# lightmeter_2.net
KiCad netlist of a schematic drawn in EAGLE
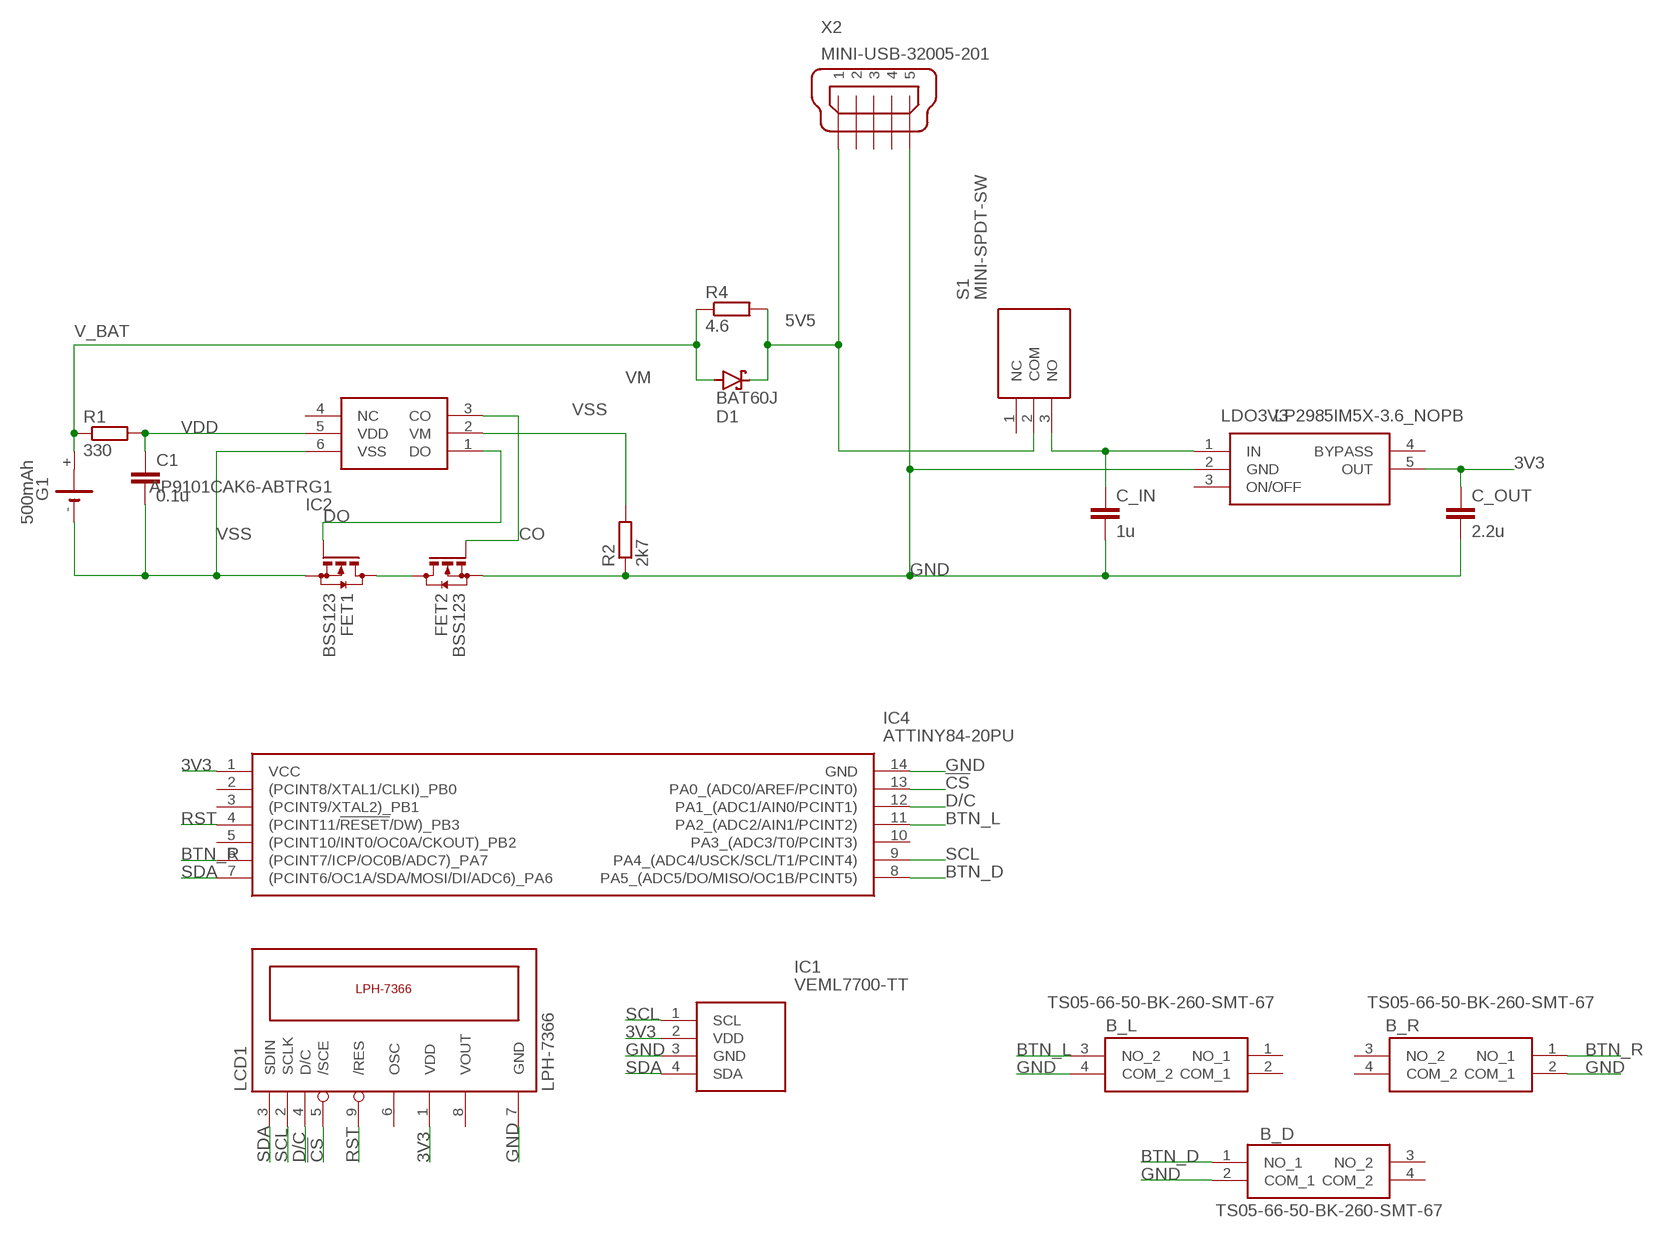
[diagram p0: schematic, sheet 1]

(export (version "E")
  (design (tool "Eeschema 10.0.6"))
  (components
    (comp (ref "B_D")
      (value "TS05-66-50-BK-260-SMT-67")
      (footprint "eagle-import:TS056650BK260SMT67")
      (fields (field (name "MOUSER_PART_NUMBER") "179-TS056650260SMT67"))
      (libsource (lib "eagle-import") (part "TS05-66-50-BK-260-SMT-67"))
    )
    (comp (ref "B_L")
      (value "TS05-66-50-BK-260-SMT-67")
      (footprint "eagle-import:TS056650BK260SMT67")
      (fields (field (name "MOUSER_PART_NUMBER") "179-TS056650260SMT67"))
      (libsource (lib "eagle-import") (part "TS05-66-50-BK-260-SMT-67"))
    )
    (comp (ref "B_R")
      (value "TS05-66-50-BK-260-SMT-67")
      (footprint "eagle-import:TS056650BK260SMT67")
      (fields (field (name "MOUSER_PART_NUMBER") "179-TS056650260SMT67"))
      (libsource (lib "eagle-import") (part "TS05-66-50-BK-260-SMT-67"))
    )
    (comp (ref "C1")
      (value "0.1u")
      (footprint "eagle-import:C3216")
      (libsource (lib "eagle-import") (part "C-EUC3216"))
    )
    (comp (ref "C_IN")
      (value "1u")
      (footprint "eagle-import:C3216")
      (libsource (lib "eagle-import") (part "C-EUC3216"))
    )
    (comp (ref "C_OUT")
      (value "2.2u")
      (footprint "eagle-import:C3216")
      (libsource (lib "eagle-import") (part "C-EUC3216"))
    )
    (comp (ref "D1")
      (value "BAT60J")
      (footprint "eagle-import:SOD323_ST")
      (libsource (lib "eagle-import") (part "BAT60J"))
    )
    (comp (ref "FET1")
      (value "BSS123")
      (footprint "eagle-import:SOT23")
      (libsource (lib "eagle-import") (part "BSS123"))
    )
    (comp (ref "FET2")
      (value "BSS123")
      (footprint "eagle-import:SOT23")
      (libsource (lib "eagle-import") (part "BSS123"))
    )
    (comp (ref "G1")
      (value "500mAh")
      (footprint "eagle-import:CR1_2")
      (libsource (lib "eagle-import") (part "CR1/2"))
    )
    (comp (ref "IC1")
      (value "VEML7700-TT")
      (footprint "eagle-import:VEML7700")
      (fields (field (name "MOUSER_PART_NUMBER") "78-VEML7700-TT"))
      (libsource (lib "eagle-import") (part "VEML7700-TT"))
    )
    (comp (ref "IC2")
      (value "AP9101CAK6-ABTRG1")
      (footprint "eagle-import:SOT95P285X140-6N")
      (fields (field (name "MOUSER_PART_NUMBER") "621-AP9101CAK6ABTRG1"))
      (libsource (lib "eagle-import") (part "AP9101CAK6-ABTRG1"))
    )
    (comp (ref "IC4")
      (value "ATTINY84-20PU")
      (footprint "eagle-import:DIP794W56P254L1918H533Q14N")
      (fields (field (name "MOUSER_PART_NUMBER") "556-ATTINY84-20PU"))
      (libsource (lib "eagle-import") (part "ATTINY84-20PU"))
    )
    (comp (ref "LCD1")
      (value "LPH-7366")
      (footprint "eagle-import:LPH-7366")
      (libsource (lib "eagle-import") (part "LPH-7366"))
    )
    (comp (ref "LDO3V3")
      (value "LP2985IM5X-3.6_NOPB")
      (footprint "eagle-import:SOT95P280X145-5N")
      (fields
        (field (name "MANUFACTURER_PART_NUMBER") "LP2985IM5X-3.6/NOPB")
        (field (name "MOUSER_PART_NUMBER") "926-LP2985IM5X36NOPB")
      )
      (libsource (lib "eagle-import") (part "LP2985IM5X-3.6_NOPB"))
    )
    (comp (ref "R1")
      (value "330")
      (footprint "eagle-import:R3216W")
      (libsource (lib "eagle-import") (part "R-EU_R3216W"))
    )
    (comp (ref "R2")
      (value "2k7")
      (footprint "eagle-import:R3216W")
      (libsource (lib "eagle-import") (part "R-EU_R3216W"))
    )
    (comp (ref "R4")
      (value "4.6")
      (footprint "eagle-import:R3216W")
      (libsource (lib "eagle-import") (part "R-EU_R3216W"))
    )
    (comp (ref "S1")
      (value "MINI-SPDT-SW")
      (footprint "eagle-import:MINISPDTSW")
      (fields (field (name "MOUSER_PART_NUMBER") "992-MINI-SPDT-SW"))
      (libsource (lib "eagle-import") (part "MINI-SPDT-SW"))
    )
    (comp (ref "X2")
      (value "MINI-USB-32005-201")
      (footprint "eagle-import:32005-201")
      (libsource (lib "eagle-import") (part "MINI-USB-32005-201"))
    )
  )
  (nets
    (net (code "1") (name "/3V3") (class "Default")
      (node (ref "C_OUT") (pin "1") (pinfunction "1_1") (pintype "passive"))
      (node (ref "IC1") (pin "2") (pinfunction "VDD_2") (pintype "bidirectional"))
      (node (ref "IC4") (pin "1") (pinfunction "VCC_1") (pintype "bidirectional"))
      (node (ref "LCD1") (pin "1") (pinfunction "VDD_1") (pintype "power_in"))
      (node (ref "LDO3V3") (pin "5") (pinfunction "OUT_5") (pintype "bidirectional"))
    )
    (net (code "2") (name "/5V5") (class "Default")
      (node (ref "D1") (pin "C") (pinfunction "C_C") (pintype "passive"))
      (node (ref "R4") (pin "2") (pinfunction "2_2") (pintype "passive"))
      (node (ref "S1") (pin "2") (pinfunction "COM_2") (pintype "bidirectional"))
      (node (ref "X2") (pin "1") (pinfunction "1_1") (pintype "passive"))
    )
    (net (code "3") (name "/BTN_D") (class "Default")
      (node (ref "B_D") (pin "1") (pinfunction "NO_1_1") (pintype "bidirectional"))
      (node (ref "IC4") (pin "8") (pinfunction "PA5_(ADC5/DO/MISO/OC1B/PCINT5)_8") (pintype "bidirectional"))
    )
    (net (code "4") (name "/BTN_L") (class "Default")
      (node (ref "B_L") (pin "3") (pinfunction "NO_2_3") (pintype "bidirectional"))
      (node (ref "IC4") (pin "11") (pinfunction "PA2_(ADC2/AIN1/PCINT2)_11") (pintype "bidirectional"))
    )
    (net (code "5") (name "/BTN_R") (class "Default")
      (node (ref "B_R") (pin "1") (pinfunction "NO_1_1") (pintype "bidirectional"))
      (node (ref "IC4") (pin "6") (pinfunction "(PCINT7/ICP/OC0B/ADC7)_PA7_6") (pintype "bidirectional"))
    )
    (net (code "6") (name "/CO") (class "Default")
      (node (ref "FET2") (pin "1") (pinfunction "G_1") (pintype "passive"))
      (node (ref "IC2") (pin "3") (pinfunction "CO_3") (pintype "bidirectional"))
    )
    (net (code "7") (name "/DO") (class "Default")
      (node (ref "FET1") (pin "1") (pinfunction "G_1") (pintype "passive"))
      (node (ref "IC2") (pin "1") (pinfunction "DO_1") (pintype "bidirectional"))
    )
    (net (code "8") (name "/D{slash}C") (class "Default")
      (node (ref "IC4") (pin "12") (pinfunction "PA1_(ADC1/AIN0/PCINT1)_12") (pintype "bidirectional"))
      (node (ref "LCD1") (pin "4") (pinfunction "D/C_4") (pintype "input"))
    )
    (net (code "9") (name "/GND") (class "Default")
      (node (ref "B_D") (pin "2") (pinfunction "COM_1_2") (pintype "bidirectional"))
      (node (ref "B_L") (pin "4") (pinfunction "COM_2_4") (pintype "bidirectional"))
      (node (ref "B_R") (pin "2") (pinfunction "COM_1_2") (pintype "bidirectional"))
      (node (ref "C_IN") (pin "2") (pinfunction "2_2") (pintype "passive"))
      (node (ref "C_OUT") (pin "2") (pinfunction "2_2") (pintype "passive"))
      (node (ref "FET2") (pin "2") (pinfunction "S_2") (pintype "passive"))
      (node (ref "IC1") (pin "3") (pinfunction "GND_3") (pintype "bidirectional"))
      (node (ref "IC4") (pin "14") (pinfunction "GND_14") (pintype "bidirectional"))
      (node (ref "LCD1") (pin "7") (pinfunction "GND_7") (pintype "power_in"))
      (node (ref "LDO3V3") (pin "2") (pinfunction "GND_2") (pintype "bidirectional"))
      (node (ref "R2") (pin "1") (pinfunction "1_1") (pintype "passive"))
      (node (ref "X2") (pin "5") (pinfunction "5_5") (pintype "passive"))
    )
    (net (code "10") (name "/RST") (class "Default")
      (node (ref "IC4") (pin "4") (pinfunction "(PCINT11/~{RESET}/DW)_PB3_4") (pintype "bidirectional"))
      (node (ref "LCD1") (pin "9") (pinfunction "/RES_9") (pintype "input"))
    )
    (net (code "11") (name "/SCL") (class "Default")
      (node (ref "IC1") (pin "1") (pinfunction "SCL_1") (pintype "bidirectional"))
      (node (ref "IC4") (pin "9") (pinfunction "PA4_(ADC4/USCK/SCL/T1/PCINT4)_9") (pintype "bidirectional"))
      (node (ref "LCD1") (pin "2") (pinfunction "SCLK_2") (pintype "input"))
    )
    (net (code "12") (name "/SDA") (class "Default")
      (node (ref "IC1") (pin "4") (pinfunction "SDA_4") (pintype "bidirectional"))
      (node (ref "IC4") (pin "7") (pinfunction "(PCINT6/OC1A/SDA/MOSI/DI/ADC6)_PA6_7") (pintype "bidirectional"))
      (node (ref "LCD1") (pin "3") (pinfunction "SDIN_3") (pintype "input"))
    )
    (net (code "13") (name "/VDD") (class "Default")
      (node (ref "C1") (pin "1") (pinfunction "1_1") (pintype "passive"))
      (node (ref "IC2") (pin "5") (pinfunction "VDD_5") (pintype "bidirectional"))
      (node (ref "R1") (pin "2") (pinfunction "2_2") (pintype "passive"))
    )
    (net (code "14") (name "/VM") (class "Default")
      (node (ref "IC2") (pin "2") (pinfunction "VM_2") (pintype "bidirectional"))
      (node (ref "R2") (pin "2") (pinfunction "2_2") (pintype "passive"))
    )
    (net (code "15") (name "/VSS") (class "Default")
      (node (ref "C1") (pin "2") (pinfunction "2_2") (pintype "passive"))
      (node (ref "FET1") (pin "2") (pinfunction "S_2") (pintype "passive"))
      (node (ref "G1") (pin "-") (pinfunction "-_-") (pintype "passive"))
      (node (ref "IC2") (pin "6") (pinfunction "VSS_6") (pintype "bidirectional"))
    )
    (net (code "16") (name "/V_BAT") (class "Default")
      (node (ref "D1") (pin "A") (pinfunction "A_A") (pintype "passive"))
      (node (ref "G1") (pin "+") (pinfunction "+_+") (pintype "passive"))
      (node (ref "R1") (pin "1") (pinfunction "1_1") (pintype "passive"))
      (node (ref "R4") (pin "1") (pinfunction "1_1") (pintype "passive"))
    )
    (net (code "17") (name "/~{CS}") (class "Default")
      (node (ref "IC4") (pin "13") (pinfunction "PA0_(ADC0/AREF/PCINT0)_13") (pintype "bidirectional"))
      (node (ref "LCD1") (pin "5") (pinfunction "/SCE_5") (pintype "input"))
    )
    (net (code "18") (name "Net-(FET1-D)") (class "Default")
      (node (ref "FET1") (pin "3") (pinfunction "D_3") (pintype "passive"))
      (node (ref "FET2") (pin "3") (pinfunction "D_3") (pintype "passive"))
    )
    (net (code "19") (name "Net-(LDO3V3-IN)") (class "Default")
      (node (ref "C_IN") (pin "1") (pinfunction "1_1") (pintype "passive"))
      (node (ref "LDO3V3") (pin "1") (pinfunction "IN_1") (pintype "bidirectional"))
      (node (ref "S1") (pin "3") (pinfunction "NO_3") (pintype "bidirectional"))
    )
    (net (code "20") (name "unconnected-(B_D-COM_2-Pad4)") (class "Default")
      (node (ref "B_D") (pin "4") (pinfunction "COM_2_4") (pintype "bidirectional"))
    )
    (net (code "21") (name "unconnected-(B_D-NO_2-Pad3)") (class "Default")
      (node (ref "B_D") (pin "3") (pinfunction "NO_2_3") (pintype "bidirectional"))
    )
    (net (code "22") (name "unconnected-(B_L-COM_1-Pad2)") (class "Default")
      (node (ref "B_L") (pin "2") (pinfunction "COM_1_2") (pintype "bidirectional"))
    )
    (net (code "23") (name "unconnected-(B_L-NO_1-Pad1)") (class "Default")
      (node (ref "B_L") (pin "1") (pinfunction "NO_1_1") (pintype "bidirectional"))
    )
    (net (code "24") (name "unconnected-(B_R-COM_2-Pad4)") (class "Default")
      (node (ref "B_R") (pin "4") (pinfunction "COM_2_4") (pintype "bidirectional"))
    )
    (net (code "25") (name "unconnected-(B_R-NO_2-Pad3)") (class "Default")
      (node (ref "B_R") (pin "3") (pinfunction "NO_2_3") (pintype "bidirectional"))
    )
    (net (code "26") (name "unconnected-(G1-+-Pad+@1)") (class "Default")
      (node (ref "G1") (pin "+@1") (pinfunction "+_+@1") (pintype "passive"))
    )
    (net (code "27") (name "unconnected-(IC2-NC-Pad4)") (class "Default")
      (node (ref "IC2") (pin "4") (pinfunction "NC_4") (pintype "no_connect"))
    )
    (net (code "28") (name "unconnected-(IC4-(PCINT8{slash}XTAL1{slash}CLKI)_PB0-Pad2)") (class "Default")
      (node (ref "IC4") (pin "2") (pinfunction "(PCINT8/XTAL1/CLKI)_PB0_2") (pintype "bidirectional"))
    )
    (net (code "29") (name "unconnected-(IC4-(PCINT9{slash}XTAL2)_PB1-Pad3)") (class "Default")
      (node (ref "IC4") (pin "3") (pinfunction "(PCINT9/XTAL2)_PB1_3") (pintype "bidirectional"))
    )
    (net (code "30") (name "unconnected-(IC4-(PCINT10{slash}INT0{slash}OC0A{slash}CKOUT)_PB2-Pad5)") (class "Default")
      (node (ref "IC4") (pin "5") (pinfunction "(PCINT10/INT0/OC0A/CKOUT)_PB2_5") (pintype "bidirectional"))
    )
    (net (code "31") (name "unconnected-(IC4-PA3_(ADC3{slash}T0{slash}PCINT3)-Pad10)") (class "Default")
      (node (ref "IC4") (pin "10") (pinfunction "PA3_(ADC3/T0/PCINT3)_10") (pintype "bidirectional"))
    )
    (net (code "32") (name "unconnected-(LCD1-OSC-Pad6)") (class "Default")
      (node (ref "LCD1") (pin "6") (pinfunction "OSC_6") (pintype "passive"))
    )
    (net (code "33") (name "unconnected-(LCD1-VOUT-Pad8)") (class "Default")
      (node (ref "LCD1") (pin "8") (pinfunction "VOUT_8") (pintype "passive"))
    )
    (net (code "34") (name "unconnected-(LDO3V3-BYPASS-Pad4)") (class "Default")
      (node (ref "LDO3V3") (pin "4") (pinfunction "BYPASS_4") (pintype "bidirectional"))
    )
    (net (code "35") (name "unconnected-(LDO3V3-ON{slash}OFF-Pad3)") (class "Default")
      (node (ref "LDO3V3") (pin "3") (pinfunction "ON/OFF_3") (pintype "bidirectional"))
    )
    (net (code "36") (name "unconnected-(S1-NC-Pad1)") (class "Default")
      (node (ref "S1") (pin "1") (pinfunction "NC_1") (pintype "no_connect"))
    )
    (net (code "37") (name "unconnected-(X2-Pad2)") (class "Default")
      (node (ref "X2") (pin "2") (pinfunction "2_2") (pintype "passive"))
    )
    (net (code "38") (name "unconnected-(X2-Pad3)") (class "Default")
      (node (ref "X2") (pin "3") (pinfunction "3_3") (pintype "passive"))
    )
    (net (code "39") (name "unconnected-(X2-Pad4)") (class "Default")
      (node (ref "X2") (pin "4") (pinfunction "4_4") (pintype "passive"))
    )
  )
)
